# TRISECT_Main.net
KiCad netlist of a schematic drawn in Altium Designer
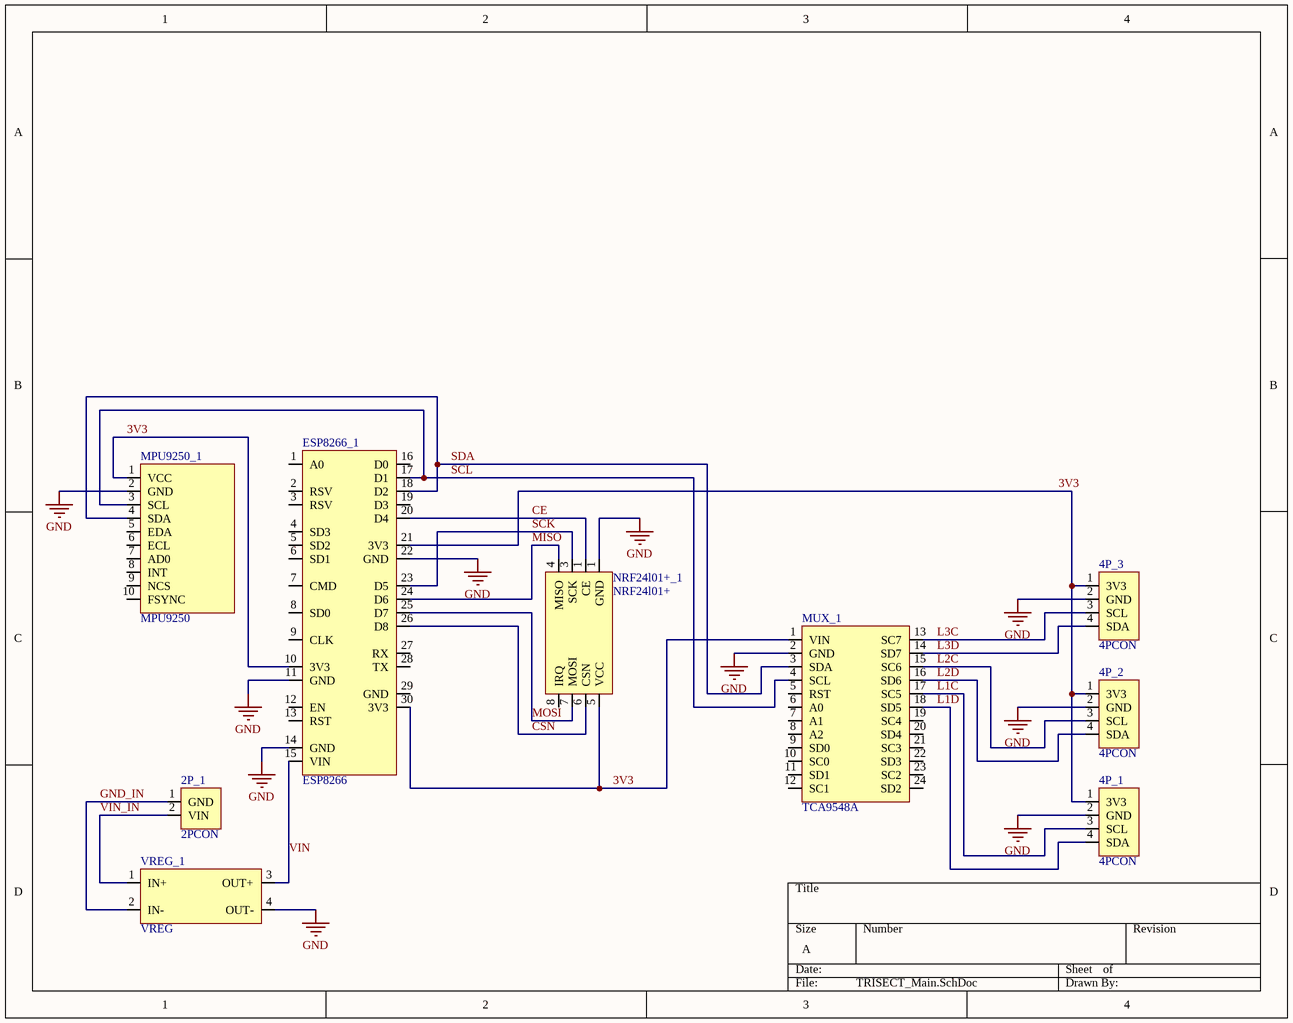
[diagram p0: TRISECT_Main.SchDoc]

(export (version "E")
  (design (tool "Eeschema 10.0.6"))
  (components
    (comp (ref "2P_1")
      (value "2PCON")
      (footprint "2PCON")
      (description "2 pin connector")
      (libsource (lib "TRISECT_Custom") (part "2PCON"))
    )
    (comp (ref "4P_1")
      (value "4PCON")
      (footprint "4PCON")
      (description "4 pin connector")
      (libsource (lib "TRISECT_Custom") (part "4PCON"))
    )
    (comp (ref "4P_2")
      (value "4PCON")
      (footprint "4PCON")
      (description "4 pin connector")
      (libsource (lib "TRISECT_Custom") (part "4PCON"))
    )
    (comp (ref "4P_3")
      (value "4PCON")
      (footprint "4PCON")
      (description "4 pin connector")
      (libsource (lib "TRISECT_Custom") (part "4PCON"))
    )
    (comp (ref "ESP8266_1")
      (value "ESP8266")
      (footprint "ESP8266")
      (description "Basic pinout for ESP8266 (NodeMCU)")
      (libsource (lib "TRISECT_Custom") (part "ESP8266"))
    )
    (comp (ref "MPU9250_1")
      (value "MPU9250")
      (footprint "MPU9250")
      (description "MPU9250 basic pinout")
      (libsource (lib "TRISECT_Custom") (part "MPU9250"))
    )
    (comp (ref "MUX_1")
      (value "TCA9548A")
      (footprint "TCA9548A")
      (description "TCA9548A multiplexer 1:8 basic pinout")
      (libsource (lib "TRISECT_Custom") (part "TCA9548A"))
    )
    (comp (ref "NRF24l01+_1")
      (value "NRF24l01+")
      (footprint "NRF24l01+")
      (description "NRF24l01+ basic pinout")
      (libsource (lib "TRISECT_Custom") (part "NRF24l01+"))
    )
    (comp (ref "VREG_1")
      (value "VREG")
      (footprint "VREG")
      (description "Voltage Regulator - basic pinout")
      (libsource (lib "TRISECT_Custom") (part "VREG"))
    )
  )
  (nets
    (net (code "1") (name "/3V3") (class "Default")
      (node (ref "4P_1") (pin "1") (pinfunction "3V3_1") (pintype "passive"))
      (node (ref "4P_2") (pin "1") (pinfunction "3V3_1") (pintype "passive"))
      (node (ref "4P_3") (pin "1") (pinfunction "3V3_1") (pintype "passive"))
      (node (ref "ESP8266_1") (pin "10") (pinfunction "3V3_10") (pintype "passive"))
      (node (ref "ESP8266_1") (pin "21") (pinfunction "3V3_21") (pintype "passive"))
      (node (ref "ESP8266_1") (pin "30") (pinfunction "3V3_30") (pintype "passive"))
      (node (ref "MPU9250_1") (pin "1") (pinfunction "VCC_1") (pintype "passive"))
      (node (ref "MUX_1") (pin "1") (pinfunction "VIN_1") (pintype "passive"))
      (node (ref "NRF24l01+_1") (pin "5") (pinfunction "VCC_5") (pintype "passive"))
    )
    (net (code "2") (name "/CE") (class "Default")
      (node (ref "ESP8266_1") (pin "20") (pinfunction "D4_20") (pintype "passive"))
      (node (ref "NRF24l01+_1") (pin "1") (pinfunction "CE_1") (pintype "passive"))
    )
    (net (code "3") (name "/CSN") (class "Default")
      (node (ref "ESP8266_1") (pin "26") (pinfunction "D8_26") (pintype "passive"))
      (node (ref "NRF24l01+_1") (pin "6") (pinfunction "CSN_6") (pintype "passive"))
    )
    (net (code "4") (name "/GND_IN") (class "Default")
      (node (ref "2P_1") (pin "1") (pinfunction "GND_1") (pintype "passive"))
      (node (ref "VREG_1") (pin "2") (pinfunction "IN-_2") (pintype "passive"))
    )
    (net (code "5") (name "/L1C") (class "Default")
      (node (ref "4P_1") (pin "3") (pinfunction "SCL_3") (pintype "passive"))
      (node (ref "MUX_1") (pin "17") (pinfunction "SC5_17") (pintype "passive"))
    )
    (net (code "6") (name "/L1D") (class "Default")
      (node (ref "4P_1") (pin "4") (pinfunction "SDA_4") (pintype "passive"))
      (node (ref "MUX_1") (pin "18") (pinfunction "SD5_18") (pintype "passive"))
    )
    (net (code "7") (name "/L2C") (class "Default")
      (node (ref "4P_2") (pin "3") (pinfunction "SCL_3") (pintype "passive"))
      (node (ref "MUX_1") (pin "15") (pinfunction "SC6_15") (pintype "passive"))
    )
    (net (code "8") (name "/L2D") (class "Default")
      (node (ref "4P_2") (pin "4") (pinfunction "SDA_4") (pintype "passive"))
      (node (ref "MUX_1") (pin "16") (pinfunction "SD6_16") (pintype "passive"))
    )
    (net (code "9") (name "/L3C") (class "Default")
      (node (ref "4P_3") (pin "3") (pinfunction "SCL_3") (pintype "passive"))
      (node (ref "MUX_1") (pin "13") (pinfunction "SC7_13") (pintype "passive"))
    )
    (net (code "10") (name "/L3D") (class "Default")
      (node (ref "4P_3") (pin "4") (pinfunction "SDA_4") (pintype "passive"))
      (node (ref "MUX_1") (pin "14") (pinfunction "SD7_14") (pintype "passive"))
    )
    (net (code "11") (name "/MISO") (class "Default")
      (node (ref "ESP8266_1") (pin "24") (pinfunction "D6_24") (pintype "passive"))
      (node (ref "NRF24l01+_1") (pin "4") (pinfunction "MISO_4") (pintype "passive"))
    )
    (net (code "12") (name "/MOSI") (class "Default")
      (node (ref "ESP8266_1") (pin "25") (pinfunction "D7_25") (pintype "passive"))
      (node (ref "NRF24l01+_1") (pin "7") (pinfunction "MOSI_7") (pintype "passive"))
    )
    (net (code "13") (name "/SCK") (class "Default")
      (node (ref "ESP8266_1") (pin "23") (pinfunction "D5_23") (pintype "passive"))
      (node (ref "NRF24l01+_1") (pin "3") (pinfunction "SCK_3") (pintype "passive"))
    )
    (net (code "14") (name "/SCL") (class "Default")
      (node (ref "ESP8266_1") (pin "17") (pinfunction "D1_17") (pintype "passive"))
      (node (ref "MPU9250_1") (pin "3") (pinfunction "SCL_3") (pintype "passive"))
      (node (ref "MUX_1") (pin "4") (pinfunction "SCL_4") (pintype "passive"))
    )
    (net (code "15") (name "/SDA") (class "Default")
      (node (ref "ESP8266_1") (pin "18") (pinfunction "D2_18") (pintype "passive"))
      (node (ref "MPU9250_1") (pin "4") (pinfunction "SDA_4") (pintype "passive"))
      (node (ref "MUX_1") (pin "3") (pinfunction "SDA_3") (pintype "passive"))
    )
    (net (code "16") (name "/VIN") (class "Default")
      (node (ref "ESP8266_1") (pin "15") (pinfunction "VIN_15") (pintype "passive"))
      (node (ref "VREG_1") (pin "3") (pinfunction "OUT+_3") (pintype "passive"))
    )
    (net (code "17") (name "/VIN_IN") (class "Default")
      (node (ref "2P_1") (pin "2") (pinfunction "VIN_2") (pintype "passive"))
      (node (ref "VREG_1") (pin "1") (pinfunction "IN+_1") (pintype "passive"))
    )
    (net (code "18") (name "GND") (class "Default")
      (node (ref "4P_1") (pin "2") (pinfunction "GND_2") (pintype "passive"))
      (node (ref "4P_2") (pin "2") (pinfunction "GND_2") (pintype "passive"))
      (node (ref "4P_3") (pin "2") (pinfunction "GND_2") (pintype "passive"))
      (node (ref "ESP8266_1") (pin "11") (pinfunction "GND_11") (pintype "passive"))
      (node (ref "ESP8266_1") (pin "14") (pinfunction "GND_14") (pintype "passive"))
      (node (ref "ESP8266_1") (pin "22") (pinfunction "GND_22") (pintype "passive"))
      (node (ref "MPU9250_1") (pin "2") (pinfunction "GND_2") (pintype "passive"))
      (node (ref "MUX_1") (pin "2") (pinfunction "GND_2") (pintype "passive"))
      (node (ref "NRF24l01+_1") (pin "1") (pinfunction "GND_1") (pintype "passive"))
      (node (ref "VREG_1") (pin "4") (pinfunction "OUT-_4") (pintype "passive"))
    )
    (net (code "19") (name "unconnected-(ESP8266_1-A0-Pad1)") (class "Default")
      (node (ref "ESP8266_1") (pin "1") (pinfunction "A0_1") (pintype "passive"))
    )
    (net (code "20") (name "unconnected-(ESP8266_1-CLK-Pad9)") (class "Default")
      (node (ref "ESP8266_1") (pin "9") (pinfunction "CLK_9") (pintype "passive"))
    )
    (net (code "21") (name "unconnected-(ESP8266_1-CMD-Pad7)") (class "Default")
      (node (ref "ESP8266_1") (pin "7") (pinfunction "CMD_7") (pintype "passive"))
    )
    (net (code "22") (name "unconnected-(ESP8266_1-D0-Pad16)") (class "Default")
      (node (ref "ESP8266_1") (pin "16") (pinfunction "D0_16") (pintype "passive"))
    )
    (net (code "23") (name "unconnected-(ESP8266_1-D3-Pad19)") (class "Default")
      (node (ref "ESP8266_1") (pin "19") (pinfunction "D3_19") (pintype "passive"))
    )
    (net (code "24") (name "unconnected-(ESP8266_1-EN-Pad12)") (class "Default")
      (node (ref "ESP8266_1") (pin "12") (pinfunction "EN_12") (pintype "passive"))
    )
    (net (code "25") (name "unconnected-(ESP8266_1-GND-Pad29)") (class "Default")
      (node (ref "ESP8266_1") (pin "29") (pinfunction "GND_29") (pintype "passive"))
    )
    (net (code "26") (name "unconnected-(ESP8266_1-RST-Pad13)") (class "Default")
      (node (ref "ESP8266_1") (pin "13") (pinfunction "RST_13") (pintype "passive"))
    )
    (net (code "27") (name "unconnected-(ESP8266_1-RSV-Pad2)") (class "Default")
      (node (ref "ESP8266_1") (pin "2") (pinfunction "RSV_2") (pintype "passive"))
    )
    (net (code "28") (name "unconnected-(ESP8266_1-RSV-Pad3)") (class "Default")
      (node (ref "ESP8266_1") (pin "3") (pinfunction "RSV_3") (pintype "passive"))
    )
    (net (code "29") (name "unconnected-(ESP8266_1-RX-Pad27)") (class "Default")
      (node (ref "ESP8266_1") (pin "27") (pinfunction "RX_27") (pintype "passive"))
    )
    (net (code "30") (name "unconnected-(ESP8266_1-SD0-Pad8)") (class "Default")
      (node (ref "ESP8266_1") (pin "8") (pinfunction "SD0_8") (pintype "passive"))
    )
    (net (code "31") (name "unconnected-(ESP8266_1-SD1-Pad6)") (class "Default")
      (node (ref "ESP8266_1") (pin "6") (pinfunction "SD1_6") (pintype "passive"))
    )
    (net (code "32") (name "unconnected-(ESP8266_1-SD2-Pad5)") (class "Default")
      (node (ref "ESP8266_1") (pin "5") (pinfunction "SD2_5") (pintype "passive"))
    )
    (net (code "33") (name "unconnected-(ESP8266_1-SD3-Pad4)") (class "Default")
      (node (ref "ESP8266_1") (pin "4") (pinfunction "SD3_4") (pintype "passive"))
    )
    (net (code "34") (name "unconnected-(ESP8266_1-TX-Pad28)") (class "Default")
      (node (ref "ESP8266_1") (pin "28") (pinfunction "TX_28") (pintype "passive"))
    )
    (net (code "35") (name "unconnected-(MPU9250_1-AD0-Pad7)") (class "Default")
      (node (ref "MPU9250_1") (pin "7") (pinfunction "AD0_7") (pintype "passive"))
    )
    (net (code "36") (name "unconnected-(MPU9250_1-ECL-Pad6)") (class "Default")
      (node (ref "MPU9250_1") (pin "6") (pinfunction "ECL_6") (pintype "passive"))
    )
    (net (code "37") (name "unconnected-(MPU9250_1-EDA-Pad5)") (class "Default")
      (node (ref "MPU9250_1") (pin "5") (pinfunction "EDA_5") (pintype "passive"))
    )
    (net (code "38") (name "unconnected-(MPU9250_1-FSYNC-Pad10)") (class "Default")
      (node (ref "MPU9250_1") (pin "10") (pinfunction "FSYNC_10") (pintype "passive"))
    )
    (net (code "39") (name "unconnected-(MPU9250_1-INT-Pad8)") (class "Default")
      (node (ref "MPU9250_1") (pin "8") (pinfunction "INT_8") (pintype "passive"))
    )
    (net (code "40") (name "unconnected-(MPU9250_1-NCS-Pad9)") (class "Default")
      (node (ref "MPU9250_1") (pin "9") (pinfunction "NCS_9") (pintype "passive"))
    )
    (net (code "41") (name "unconnected-(MUX_1-A0-Pad6)") (class "Default")
      (node (ref "MUX_1") (pin "6") (pinfunction "A0_6") (pintype "passive"))
    )
    (net (code "42") (name "unconnected-(MUX_1-A1-Pad7)") (class "Default")
      (node (ref "MUX_1") (pin "7") (pinfunction "A1_7") (pintype "passive"))
    )
    (net (code "43") (name "unconnected-(MUX_1-A2-Pad8)") (class "Default")
      (node (ref "MUX_1") (pin "8") (pinfunction "A2_8") (pintype "passive"))
    )
    (net (code "44") (name "unconnected-(MUX_1-RST-Pad5)") (class "Default")
      (node (ref "MUX_1") (pin "5") (pinfunction "RST_5") (pintype "passive"))
    )
    (net (code "45") (name "unconnected-(MUX_1-SC0-Pad10)") (class "Default")
      (node (ref "MUX_1") (pin "10") (pinfunction "SC0_10") (pintype "passive"))
    )
    (net (code "46") (name "unconnected-(MUX_1-SC1-Pad12)") (class "Default")
      (node (ref "MUX_1") (pin "12") (pinfunction "SC1_12") (pintype "passive"))
    )
    (net (code "47") (name "unconnected-(MUX_1-SC2-Pad23)") (class "Default")
      (node (ref "MUX_1") (pin "23") (pinfunction "SC2_23") (pintype "passive"))
    )
    (net (code "48") (name "unconnected-(MUX_1-SC3-Pad21)") (class "Default")
      (node (ref "MUX_1") (pin "21") (pinfunction "SC3_21") (pintype "passive"))
    )
    (net (code "49") (name "unconnected-(MUX_1-SC4-Pad19)") (class "Default")
      (node (ref "MUX_1") (pin "19") (pinfunction "SC4_19") (pintype "passive"))
    )
    (net (code "50") (name "unconnected-(MUX_1-SD0-Pad9)") (class "Default")
      (node (ref "MUX_1") (pin "9") (pinfunction "SD0_9") (pintype "passive"))
    )
    (net (code "51") (name "unconnected-(MUX_1-SD1-Pad11)") (class "Default")
      (node (ref "MUX_1") (pin "11") (pinfunction "SD1_11") (pintype "passive"))
    )
    (net (code "52") (name "unconnected-(MUX_1-SD2-Pad24)") (class "Default")
      (node (ref "MUX_1") (pin "24") (pinfunction "SD2_24") (pintype "passive"))
    )
    (net (code "53") (name "unconnected-(MUX_1-SD3-Pad22)") (class "Default")
      (node (ref "MUX_1") (pin "22") (pinfunction "SD3_22") (pintype "passive"))
    )
    (net (code "54") (name "unconnected-(MUX_1-SD4-Pad20)") (class "Default")
      (node (ref "MUX_1") (pin "20") (pinfunction "SD4_20") (pintype "passive"))
    )
    (net (code "55") (name "unconnected-(NRF24l01+_1-IRQ-Pad8)") (class "Default")
      (node (ref "NRF24l01+_1") (pin "8") (pinfunction "IRQ_8") (pintype "passive"))
    )
  )
)
